# top_schem_rev4.net
KiCad netlist of a schematic drawn in Altium Designer
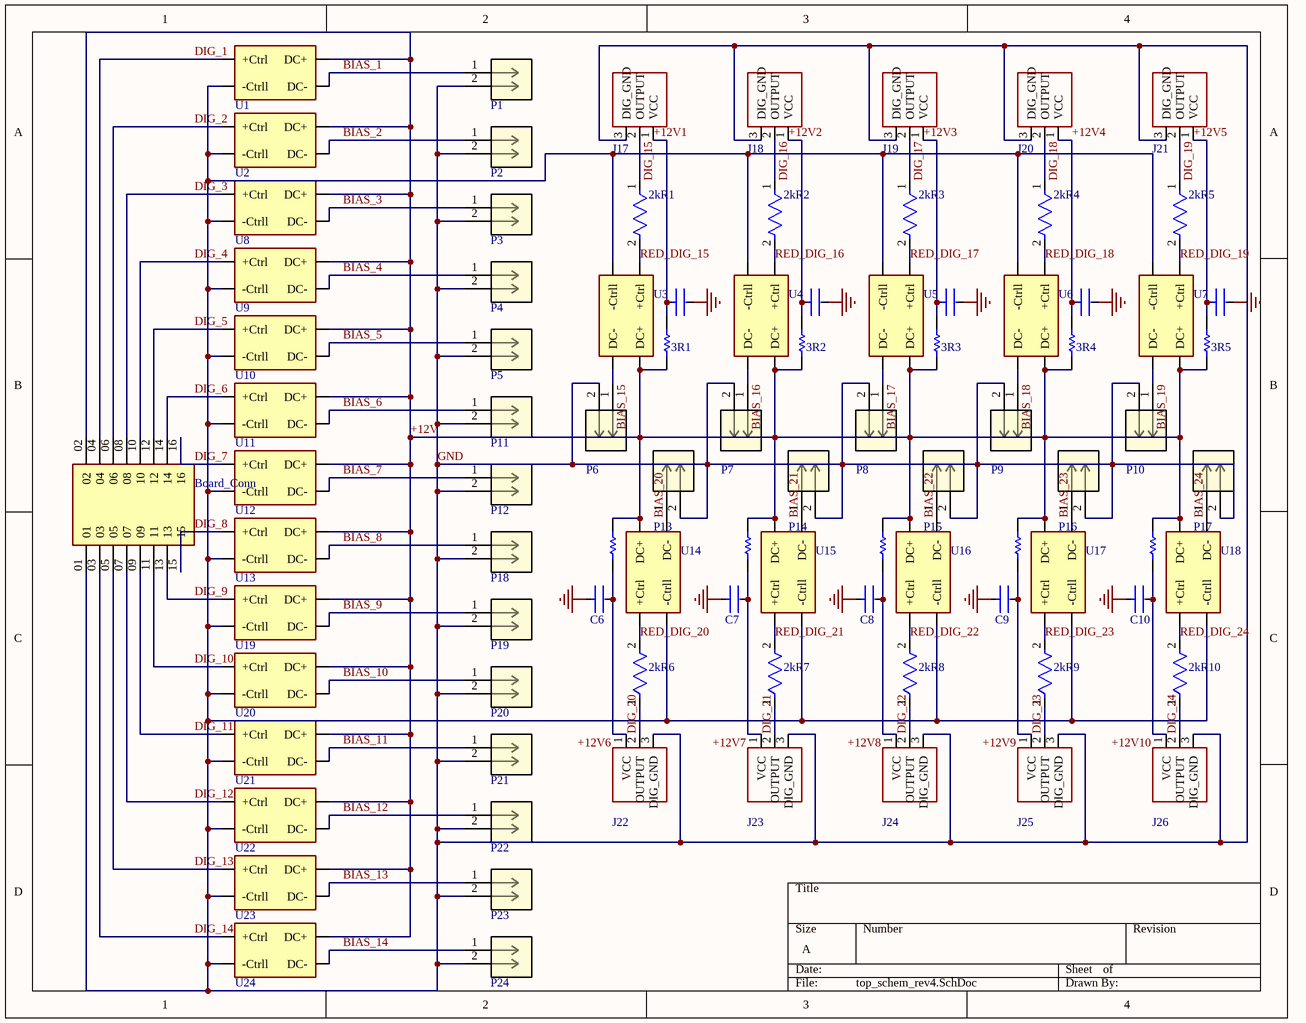
[diagram p0: top_schem_rev4.SchDoc]

(export (version "E")
  (design (tool "Eeschema 10.0.6"))
  (components
    (comp (ref "2kR1")
      (value "CRCW06031K80FKEA")
      (footprint "2kOhm")
      (description "Res Thick Film 0603 1.8K Ohm 1% 1/10W ±100ppm/°C Molded SMD Paper T/R")
      (fields (field (name "MANUFACTURER") "Vishay") (field (name "TOLERANCE") "1%"))
      (libsource (lib "ps_schlib") (part "CRCW06031K80FKEA"))
    )
    (comp (ref "2kR2")
      (value "CRCW06031K80FKEA")
      (footprint "2kOhm")
      (description "Res Thick Film 0603 1.8K Ohm 1% 1/10W ±100ppm/°C Molded SMD Paper T/R")
      (fields (field (name "MANUFACTURER") "Vishay") (field (name "TOLERANCE") "1%"))
      (libsource (lib "ps_schlib") (part "CRCW06031K80FKEA"))
    )
    (comp (ref "2kR3")
      (value "CRCW06031K80FKEA")
      (footprint "2kOhm")
      (description "Res Thick Film 0603 1.8K Ohm 1% 1/10W ±100ppm/°C Molded SMD Paper T/R")
      (fields (field (name "MANUFACTURER") "Vishay") (field (name "TOLERANCE") "1%"))
      (libsource (lib "ps_schlib") (part "CRCW06031K80FKEA"))
    )
    (comp (ref "2kR4")
      (value "CRCW06031K80FKEA")
      (footprint "2kOhm")
      (description "Res Thick Film 0603 1.8K Ohm 1% 1/10W ±100ppm/°C Molded SMD Paper T/R")
      (fields (field (name "MANUFACTURER") "Vishay") (field (name "TOLERANCE") "1%"))
      (libsource (lib "ps_schlib") (part "CRCW06031K80FKEA"))
    )
    (comp (ref "2kR5")
      (value "CRCW06031K80FKEA")
      (footprint "2kOhm")
      (description "Res Thick Film 0603 1.8K Ohm 1% 1/10W ±100ppm/°C Molded SMD Paper T/R")
      (fields (field (name "MANUFACTURER") "Vishay") (field (name "TOLERANCE") "1%"))
      (libsource (lib "ps_schlib") (part "CRCW06031K80FKEA"))
    )
    (comp (ref "2kR6")
      (value "CRCW06031K80FKEA")
      (footprint "2kOhm")
      (description "Res Thick Film 0603 1.8K Ohm 1% 1/10W ±100ppm/°C Molded SMD Paper T/R")
      (fields (field (name "MANUFACTURER") "Vishay") (field (name "TOLERANCE") "1%"))
      (libsource (lib "ps_schlib") (part "CRCW06031K80FKEA"))
    )
    (comp (ref "2kR7")
      (value "CRCW06031K80FKEA")
      (footprint "2kOhm")
      (description "Res Thick Film 0603 1.8K Ohm 1% 1/10W ±100ppm/°C Molded SMD Paper T/R")
      (fields (field (name "MANUFACTURER") "Vishay") (field (name "TOLERANCE") "1%"))
      (libsource (lib "ps_schlib") (part "CRCW06031K80FKEA"))
    )
    (comp (ref "2kR8")
      (value "CRCW06031K80FKEA")
      (footprint "2kOhm")
      (description "Res Thick Film 0603 1.8K Ohm 1% 1/10W ±100ppm/°C Molded SMD Paper T/R")
      (fields (field (name "MANUFACTURER") "Vishay") (field (name "TOLERANCE") "1%"))
      (libsource (lib "ps_schlib") (part "CRCW06031K80FKEA"))
    )
    (comp (ref "2kR9")
      (value "CRCW06031K80FKEA")
      (footprint "2kOhm")
      (description "Res Thick Film 0603 1.8K Ohm 1% 1/10W ±100ppm/°C Molded SMD Paper T/R")
      (fields (field (name "MANUFACTURER") "Vishay") (field (name "TOLERANCE") "1%"))
      (libsource (lib "ps_schlib") (part "CRCW06031K80FKEA"))
    )
    (comp (ref "2kR10")
      (value "CRCW06031K80FKEA")
      (footprint "2kOhm")
      (description "Res Thick Film 0603 1.8K Ohm 1% 1/10W ±100ppm/°C Molded SMD Paper T/R")
      (fields (field (name "MANUFACTURER") "Vishay") (field (name "TOLERANCE") "1%"))
      (libsource (lib "ps_schlib") (part "CRCW06031K80FKEA"))
    )
    (comp (ref "3R1")
      (value "ERJ-2BQJR30X")
      (footprint "03 Ohm")
      (description "RES 0.3 OHM 5% 1/6W 0402")
      (fields (field (name "MANUFACTURER") "Panasonic") (field (name "TOLERANCE") "5%"))
      (libsource (lib "ps_schlib") (part "ERJ-2BQJR30X"))
    )
    (comp (ref "3R2")
      (value "ERJ-2BQJR30X")
      (footprint "03 Ohm")
      (description "RES 0.3 OHM 5% 1/6W 0402")
      (fields (field (name "MANUFACTURER") "Panasonic") (field (name "TOLERANCE") "5%"))
      (libsource (lib "ps_schlib") (part "ERJ-2BQJR30X"))
    )
    (comp (ref "3R3")
      (value "ERJ-2BQJR30X")
      (footprint "03 Ohm")
      (description "RES 0.3 OHM 5% 1/6W 0402")
      (fields (field (name "MANUFACTURER") "Panasonic") (field (name "TOLERANCE") "5%"))
      (libsource (lib "ps_schlib") (part "ERJ-2BQJR30X"))
    )
    (comp (ref "3R4")
      (value "ERJ-2BQJR30X")
      (footprint "03 Ohm")
      (description "RES 0.3 OHM 5% 1/6W 0402")
      (fields (field (name "MANUFACTURER") "Panasonic") (field (name "TOLERANCE") "5%"))
      (libsource (lib "ps_schlib") (part "ERJ-2BQJR30X"))
    )
    (comp (ref "3R5")
      (value "ERJ-2BQJR30X")
      (footprint "03 Ohm")
      (description "RES 0.3 OHM 5% 1/6W 0402")
      (fields (field (name "MANUFACTURER") "Panasonic") (field (name "TOLERANCE") "5%"))
      (libsource (lib "ps_schlib") (part "ERJ-2BQJR30X"))
    )
    (comp (ref "3R6")
      (value "ERJ-2BQJR30X")
      (footprint "03 Ohm")
      (description "RES 0.3 OHM 5% 1/6W 0402")
      (fields (field (name "MANUFACTURER") "Panasonic") (field (name "TOLERANCE") "5%"))
      (libsource (lib "ps_schlib") (part "ERJ-2BQJR30X"))
    )
    (comp (ref "3R7")
      (value "ERJ-2BQJR30X")
      (footprint "03 Ohm")
      (description "RES 0.3 OHM 5% 1/6W 0402")
      (fields (field (name "MANUFACTURER") "Panasonic") (field (name "TOLERANCE") "5%"))
      (libsource (lib "ps_schlib") (part "ERJ-2BQJR30X"))
    )
    (comp (ref "3R8")
      (value "ERJ-2BQJR30X")
      (footprint "03 Ohm")
      (description "RES 0.3 OHM 5% 1/6W 0402")
      (fields (field (name "MANUFACTURER") "Panasonic") (field (name "TOLERANCE") "5%"))
      (libsource (lib "ps_schlib") (part "ERJ-2BQJR30X"))
    )
    (comp (ref "3R9")
      (value "ERJ-2BQJR30X")
      (footprint "03 Ohm")
      (description "RES 0.3 OHM 5% 1/6W 0402")
      (fields (field (name "MANUFACTURER") "Panasonic") (field (name "TOLERANCE") "5%"))
      (libsource (lib "ps_schlib") (part "ERJ-2BQJR30X"))
    )
    (comp (ref "3R10")
      (value "ERJ-2BQJR30X")
      (footprint "03 Ohm")
      (description "RES 0.3 OHM 5% 1/6W 0402")
      (fields (field (name "MANUFACTURER") "Panasonic") (field (name "TOLERANCE") "5%"))
      (libsource (lib "ps_schlib") (part "ERJ-2BQJR30X"))
    )
    (comp (ref "Board_Conn")
      (value "SSM-108-X-DV")
      (footprint "16 pin header")
      (libsource (lib "ps_schlib") (part "SSM-108-X-DV"))
    )
    (comp (ref "C1")
      (value "C0805C104K5RACTU")
      (footprint "100nF")
      (description "Cap Ceramic 0.1uF 50V X7R 10% SMD 2.0 x 1.2 mm 125 C Paper T/R")
      (fields (field (name "MANUFACTURER") "KEMET") (field (name "TOLERANCE") "10%"))
      (libsource (lib "ps_schlib") (part "C0805C104K5RACTU"))
    )
    (comp (ref "C2")
      (value "C0805C104K5RACTU")
      (footprint "100nF")
      (description "Cap Ceramic 0.1uF 50V X7R 10% SMD 2.0 x 1.2 mm 125 C Paper T/R")
      (fields (field (name "MANUFACTURER") "KEMET") (field (name "TOLERANCE") "10%"))
      (libsource (lib "ps_schlib") (part "C0805C104K5RACTU"))
    )
    (comp (ref "C3")
      (value "C0805C104K5RACTU")
      (footprint "100nF")
      (description "Cap Ceramic 0.1uF 50V X7R 10% SMD 2.0 x 1.2 mm 125 C Paper T/R")
      (fields (field (name "MANUFACTURER") "KEMET") (field (name "TOLERANCE") "10%"))
      (libsource (lib "ps_schlib") (part "C0805C104K5RACTU"))
    )
    (comp (ref "C4")
      (value "C0805C104K5RACTU")
      (footprint "100nF")
      (description "Cap Ceramic 0.1uF 50V X7R 10% SMD 2.0 x 1.2 mm 125 C Paper T/R")
      (fields (field (name "MANUFACTURER") "KEMET") (field (name "TOLERANCE") "10%"))
      (libsource (lib "ps_schlib") (part "C0805C104K5RACTU"))
    )
    (comp (ref "C5")
      (value "C0805C104K5RACTU")
      (footprint "100nF")
      (description "Cap Ceramic 0.1uF 50V X7R 10% SMD 2.0 x 1.2 mm 125 C Paper T/R")
      (fields (field (name "MANUFACTURER") "KEMET") (field (name "TOLERANCE") "10%"))
      (libsource (lib "ps_schlib") (part "C0805C104K5RACTU"))
    )
    (comp (ref "C6")
      (value "C0805C104K5RACTU")
      (footprint "100nF")
      (description "Cap Ceramic 0.1uF 50V X7R 10% SMD 2.0 x 1.2 mm 125 C Paper T/R")
      (fields (field (name "MANUFACTURER") "KEMET") (field (name "TOLERANCE") "10%"))
      (libsource (lib "ps_schlib") (part "C0805C104K5RACTU"))
    )
    (comp (ref "C7")
      (value "C0805C104K5RACTU")
      (footprint "100nF")
      (description "Cap Ceramic 0.1uF 50V X7R 10% SMD 2.0 x 1.2 mm 125 C Paper T/R")
      (fields (field (name "MANUFACTURER") "KEMET") (field (name "TOLERANCE") "10%"))
      (libsource (lib "ps_schlib") (part "C0805C104K5RACTU"))
    )
    (comp (ref "C8")
      (value "C0805C104K5RACTU")
      (footprint "100nF")
      (description "Cap Ceramic 0.1uF 50V X7R 10% SMD 2.0 x 1.2 mm 125 C Paper T/R")
      (fields (field (name "MANUFACTURER") "KEMET") (field (name "TOLERANCE") "10%"))
      (libsource (lib "ps_schlib") (part "C0805C104K5RACTU"))
    )
    (comp (ref "C9")
      (value "C0805C104K5RACTU")
      (footprint "100nF")
      (description "Cap Ceramic 0.1uF 50V X7R 10% SMD 2.0 x 1.2 mm 125 C Paper T/R")
      (fields (field (name "MANUFACTURER") "KEMET") (field (name "TOLERANCE") "10%"))
      (libsource (lib "ps_schlib") (part "C0805C104K5RACTU"))
    )
    (comp (ref "C10")
      (value "C0805C104K5RACTU")
      (footprint "100nF")
      (description "Cap Ceramic 0.1uF 50V X7R 10% SMD 2.0 x 1.2 mm 125 C Paper T/R")
      (fields (field (name "MANUFACTURER") "KEMET") (field (name "TOLERANCE") "10%"))
      (libsource (lib "ps_schlib") (part "C0805C104K5RACTU"))
    )
    (comp (ref "J17")
      (value "IF-D95T")
      (footprint "IF-D95")
      (description "DETECTOR PHOTOLOGIC TTL/CMOS")
      (fields (field (name "MANUFACTURER") "Industrial Fiber Optics"))
      (libsource (lib "ps_schlib") (part "IF-D95T"))
    )
    (comp (ref "J18")
      (value "IF-D95T")
      (footprint "IF-D95")
      (description "DETECTOR PHOTOLOGIC TTL/CMOS")
      (fields (field (name "MANUFACTURER") "Industrial Fiber Optics"))
      (libsource (lib "ps_schlib") (part "IF-D95T"))
    )
    (comp (ref "J19")
      (value "IF-D95T")
      (footprint "IF-D95")
      (description "DETECTOR PHOTOLOGIC TTL/CMOS")
      (fields (field (name "MANUFACTURER") "Industrial Fiber Optics"))
      (libsource (lib "ps_schlib") (part "IF-D95T"))
    )
    (comp (ref "J20")
      (value "IF-D95T")
      (footprint "IF-D95")
      (description "DETECTOR PHOTOLOGIC TTL/CMOS")
      (fields (field (name "MANUFACTURER") "Industrial Fiber Optics"))
      (libsource (lib "ps_schlib") (part "IF-D95T"))
    )
    (comp (ref "J21")
      (value "IF-D95T")
      (footprint "IF-D95")
      (description "DETECTOR PHOTOLOGIC TTL/CMOS")
      (fields (field (name "MANUFACTURER") "Industrial Fiber Optics"))
      (libsource (lib "ps_schlib") (part "IF-D95T"))
    )
    (comp (ref "J22")
      (value "IF-D95T")
      (footprint "IF-D95")
      (description "DETECTOR PHOTOLOGIC TTL/CMOS")
      (fields (field (name "MANUFACTURER") "Industrial Fiber Optics"))
      (libsource (lib "ps_schlib") (part "IF-D95T"))
    )
    (comp (ref "J23")
      (value "IF-D95T")
      (footprint "IF-D95")
      (description "DETECTOR PHOTOLOGIC TTL/CMOS")
      (fields (field (name "MANUFACTURER") "Industrial Fiber Optics"))
      (libsource (lib "ps_schlib") (part "IF-D95T"))
    )
    (comp (ref "J24")
      (value "IF-D95T")
      (footprint "IF-D95")
      (description "DETECTOR PHOTOLOGIC TTL/CMOS")
      (fields (field (name "MANUFACTURER") "Industrial Fiber Optics"))
      (libsource (lib "ps_schlib") (part "IF-D95T"))
    )
    (comp (ref "J25")
      (value "IF-D95T")
      (footprint "IF-D95")
      (description "DETECTOR PHOTOLOGIC TTL/CMOS")
      (fields (field (name "MANUFACTURER") "Industrial Fiber Optics"))
      (libsource (lib "ps_schlib") (part "IF-D95T"))
    )
    (comp (ref "J26")
      (value "IF-D95T")
      (footprint "IF-D95")
      (description "DETECTOR PHOTOLOGIC TTL/CMOS")
      (fields (field (name "MANUFACTURER") "Industrial Fiber Optics"))
      (libsource (lib "ps_schlib") (part "IF-D95T"))
    )
    (comp (ref "P1")
      (value "1054311102")
      (footprint "CONN_1054311102_MOL")
      (fields (field (name "MANUFACTURER") "Molex"))
      (libsource (lib "ps_schlib") (part "1054311102"))
    )
    (comp (ref "P2")
      (value "1054311102")
      (footprint "CONN_1054311102_MOL")
      (fields (field (name "MANUFACTURER") "Molex"))
      (libsource (lib "ps_schlib") (part "1054311102"))
    )
    (comp (ref "P3")
      (value "1054311102")
      (footprint "CONN_1054311102_MOL")
      (fields (field (name "MANUFACTURER") "Molex"))
      (libsource (lib "ps_schlib") (part "1054311102"))
    )
    (comp (ref "P4")
      (value "1054311102")
      (footprint "CONN_1054311102_MOL")
      (fields (field (name "MANUFACTURER") "Molex"))
      (libsource (lib "ps_schlib") (part "1054311102"))
    )
    (comp (ref "P5")
      (value "1054311102")
      (footprint "CONN_1054311102_MOL")
      (fields (field (name "MANUFACTURER") "Molex"))
      (libsource (lib "ps_schlib") (part "1054311102"))
    )
    (comp (ref "P6")
      (value "1054311102")
      (footprint "CONN_1054311102_MOL")
      (fields (field (name "MANUFACTURER") "Molex"))
      (libsource (lib "") (part "1054311102_1"))
    )
    (comp (ref "P7")
      (value "1054311102")
      (footprint "CONN_1054311102_MOL")
      (fields (field (name "MANUFACTURER") "Molex"))
      (libsource (lib "") (part "1054311102_1"))
    )
    (comp (ref "P8")
      (value "1054311102")
      (footprint "CONN_1054311102_MOL")
      (fields (field (name "MANUFACTURER") "Molex"))
      (libsource (lib "") (part "1054311102_1"))
    )
    (comp (ref "P9")
      (value "1054311102")
      (footprint "CONN_1054311102_MOL")
      (fields (field (name "MANUFACTURER") "Molex"))
      (libsource (lib "") (part "1054311102_1"))
    )
    (comp (ref "P10")
      (value "1054311102")
      (footprint "CONN_1054311102_MOL")
      (fields (field (name "MANUFACTURER") "Molex"))
      (libsource (lib "") (part "1054311102_1"))
    )
    (comp (ref "P11")
      (value "1054311102")
      (footprint "CONN_1054311102_MOL")
      (fields (field (name "MANUFACTURER") "Molex"))
      (libsource (lib "ps_schlib") (part "1054311102"))
    )
    (comp (ref "P12")
      (value "1054311102")
      (footprint "CONN_1054311102_MOL")
      (fields (field (name "MANUFACTURER") "Molex"))
      (libsource (lib "ps_schlib") (part "1054311102"))
    )
    (comp (ref "P13")
      (value "1054311102")
      (footprint "CONN_1054311102_MOL")
      (fields (field (name "MANUFACTURER") "Molex"))
      (libsource (lib "") (part "1054311102_2"))
    )
    (comp (ref "P14")
      (value "1054311102")
      (footprint "CONN_1054311102_MOL")
      (fields (field (name "MANUFACTURER") "Molex"))
      (libsource (lib "") (part "1054311102_2"))
    )
    (comp (ref "P15")
      (value "1054311102")
      (footprint "CONN_1054311102_MOL")
      (fields (field (name "MANUFACTURER") "Molex"))
      (libsource (lib "") (part "1054311102_2"))
    )
    (comp (ref "P16")
      (value "1054311102")
      (footprint "CONN_1054311102_MOL")
      (fields (field (name "MANUFACTURER") "Molex"))
      (libsource (lib "") (part "1054311102_2"))
    )
    (comp (ref "P17")
      (value "1054311102")
      (footprint "CONN_1054311102_MOL")
      (fields (field (name "MANUFACTURER") "Molex"))
      (libsource (lib "") (part "1054311102_2"))
    )
    (comp (ref "P18")
      (value "1054311102")
      (footprint "CONN_1054311102_MOL")
      (fields (field (name "MANUFACTURER") "Molex"))
      (libsource (lib "ps_schlib") (part "1054311102"))
    )
    (comp (ref "P19")
      (value "1054311102")
      (footprint "CONN_1054311102_MOL")
      (fields (field (name "MANUFACTURER") "Molex"))
      (libsource (lib "ps_schlib") (part "1054311102"))
    )
    (comp (ref "P20")
      (value "1054311102")
      (footprint "CONN_1054311102_MOL")
      (fields (field (name "MANUFACTURER") "Molex"))
      (libsource (lib "ps_schlib") (part "1054311102"))
    )
    (comp (ref "P21")
      (value "1054311102")
      (footprint "CONN_1054311102_MOL")
      (fields (field (name "MANUFACTURER") "Molex"))
      (libsource (lib "ps_schlib") (part "1054311102"))
    )
    (comp (ref "P22")
      (value "1054311102")
      (footprint "CONN_1054311102_MOL")
      (fields (field (name "MANUFACTURER") "Molex"))
      (libsource (lib "ps_schlib") (part "1054311102"))
    )
    (comp (ref "P23")
      (value "1054311102")
      (footprint "CONN_1054311102_MOL")
      (fields (field (name "MANUFACTURER") "Molex"))
      (libsource (lib "ps_schlib") (part "1054311102"))
    )
    (comp (ref "P24")
      (value "1054311102")
      (footprint "CONN_1054311102_MOL")
      (fields (field (name "MANUFACTURER") "Molex"))
      (libsource (lib "ps_schlib") (part "1054311102"))
    )
    (comp (ref "U1")
      (value "Solid state relay")
      (footprint "CPC1002N")
      (libsource (lib "") (part "CPC1002N_1"))
    )
    (comp (ref "U2")
      (value "Solid state relay")
      (footprint "CPC1002N")
      (libsource (lib "") (part "CPC1002N_1"))
    )
    (comp (ref "U3")
      (value "Solid state relay")
      (footprint "CPC1002N")
      (libsource (lib "") (part "CPC1002N_2"))
    )
    (comp (ref "U4")
      (value "Solid state relay")
      (footprint "CPC1002N")
      (libsource (lib "") (part "CPC1002N_2"))
    )
    (comp (ref "U5")
      (value "Solid state relay")
      (footprint "CPC1002N")
      (libsource (lib "") (part "CPC1002N_2"))
    )
    (comp (ref "U6")
      (value "Solid state relay")
      (footprint "CPC1002N")
      (libsource (lib "") (part "CPC1002N_2"))
    )
    (comp (ref "U7")
      (value "Solid state relay")
      (footprint "CPC1002N")
      (libsource (lib "") (part "CPC1002N_2"))
    )
    (comp (ref "U8")
      (value "Solid state relay")
      (footprint "CPC1002N")
      (libsource (lib "") (part "CPC1002N_1"))
    )
    (comp (ref "U9")
      (value "Solid state relay")
      (footprint "CPC1002N")
      (libsource (lib "") (part "CPC1002N_1"))
    )
    (comp (ref "U10")
      (value "Solid state relay")
      (footprint "CPC1002N")
      (libsource (lib "") (part "CPC1002N_1"))
    )
    (comp (ref "U11")
      (value "Solid state relay")
      (footprint "CPC1002N")
      (libsource (lib "") (part "CPC1002N_1"))
    )
    (comp (ref "U12")
      (value "Solid state relay")
      (footprint "CPC1002N")
      (libsource (lib "") (part "CPC1002N_1"))
    )
    (comp (ref "U13")
      (value "Solid state relay")
      (footprint "CPC1002N")
      (libsource (lib "") (part "CPC1002N_1"))
    )
    (comp (ref "U14")
      (value "Solid state relay")
      (footprint "CPC1002N")
      (libsource (lib "ps_schlib") (part "CPC1002N"))
    )
    (comp (ref "U15")
      (value "Solid state relay")
      (footprint "CPC1002N")
      (libsource (lib "ps_schlib") (part "CPC1002N"))
    )
    (comp (ref "U16")
      (value "Solid state relay")
      (footprint "CPC1002N")
      (libsource (lib "ps_schlib") (part "CPC1002N"))
    )
    (comp (ref "U17")
      (value "Solid state relay")
      (footprint "CPC1002N")
      (libsource (lib "ps_schlib") (part "CPC1002N"))
    )
    (comp (ref "U18")
      (value "Solid state relay")
      (footprint "CPC1002N")
      (libsource (lib "ps_schlib") (part "CPC1002N"))
    )
    (comp (ref "U19")
      (value "Solid state relay")
      (footprint "CPC1002N")
      (libsource (lib "") (part "CPC1002N_1"))
    )
    (comp (ref "U20")
      (value "Solid state relay")
      (footprint "CPC1002N")
      (libsource (lib "") (part "CPC1002N_1"))
    )
    (comp (ref "U21")
      (value "Solid state relay")
      (footprint "CPC1002N")
      (libsource (lib "") (part "CPC1002N_1"))
    )
    (comp (ref "U22")
      (value "Solid state relay")
      (footprint "CPC1002N")
      (libsource (lib "") (part "CPC1002N_1"))
    )
    (comp (ref "U23")
      (value "Solid state relay")
      (footprint "CPC1002N")
      (libsource (lib "") (part "CPC1002N_1"))
    )
    (comp (ref "U24")
      (value "Solid state relay")
      (footprint "CPC1002N")
      (libsource (lib "") (part "CPC1002N_1"))
    )
  )
  (nets
    (net (code "1") (name "/+12V") (class "Default")
      (node (ref "3R1") (pin "1") (pinfunction "1_1") (pintype "passive"))
      (node (ref "3R10") (pin "2") (pinfunction "2_2") (pintype "passive"))
      (node (ref "3R2") (pin "1") (pinfunction "1_1") (pintype "passive"))
      (node (ref "3R3") (pin "1") (pinfunction "1_1") (pintype "passive"))
      (node (ref "3R4") (pin "1") (pinfunction "1_1") (pintype "passive"))
      (node (ref "3R5") (pin "1") (pinfunction "1_1") (pintype "passive"))
      (node (ref "3R6") (pin "2") (pinfunction "2_2") (pintype "passive"))
      (node (ref "3R7") (pin "2") (pinfunction "2_2") (pintype "passive"))
      (node (ref "3R8") (pin "2") (pinfunction "2_2") (pintype "passive"))
      (node (ref "3R9") (pin "2") (pinfunction "2_2") (pintype "passive"))
      (node (ref "Board_Conn") (pin "02") (pinfunction "02_02") (pintype "passive"))
      (node (ref "U1") (pin "4") (pinfunction "DC+_4") (pintype "passive"))
      (node (ref "U10") (pin "4") (pinfunction "DC+_4") (pintype "passive"))
      (node (ref "U11") (pin "4") (pinfunction "DC+_4") (pintype "passive"))
      (node (ref "U12") (pin "4") (pinfunction "DC+_4") (pintype "passive"))
      (node (ref "U13") (pin "4") (pinfunction "DC+_4") (pintype "passive"))
      (node (ref "U14") (pin "4") (pinfunction "DC+_4") (pintype "passive"))
      (node (ref "U15") (pin "4") (pinfunction "DC+_4") (pintype "passive"))
      (node (ref "U16") (pin "4") (pinfunction "DC+_4") (pintype "passive"))
      (node (ref "U17") (pin "4") (pinfunction "DC+_4") (pintype "passive"))
      (node (ref "U18") (pin "4") (pinfunction "DC+_4") (pintype "passive"))
      (node (ref "U19") (pin "4") (pinfunction "DC+_4") (pintype "passive"))
      (node (ref "U2") (pin "4") (pinfunction "DC+_4") (pintype "passive"))
      (node (ref "U20") (pin "4") (pinfunction "DC+_4") (pintype "passive"))
      (node (ref "U21") (pin "4") (pinfunction "DC+_4") (pintype "passive"))
      (node (ref "U22") (pin "4") (pinfunction "DC+_4") (pintype "passive"))
      (node (ref "U23") (pin "4") (pinfunction "DC+_4") (pintype "passive"))
      (node (ref "U24") (pin "4") (pinfunction "DC+_4") (pintype "passive"))
      (node (ref "U3") (pin "4") (pinfunction "DC+_4") (pintype "passive"))
      (node (ref "U4") (pin "4") (pinfunction "DC+_4") (pintype "passive"))
      (node (ref "U5") (pin "4") (pinfunction "DC+_4") (pintype "passive"))
      (node (ref "U6") (pin "4") (pinfunction "DC+_4") (pintype "passive"))
      (node (ref "U7") (pin "4") (pinfunction "DC+_4") (pintype "passive"))
      (node (ref "U8") (pin "4") (pinfunction "DC+_4") (pintype "passive"))
      (node (ref "U9") (pin "4") (pinfunction "DC+_4") (pintype "passive"))
    )
    (net (code "2") (name "/+12V1") (class "Default")
      (node (ref "3R1") (pin "2") (pinfunction "2_2") (pintype "passive"))
      (node (ref "C1") (pin "1") (pinfunction "1_1") (pintype "passive"))
      (node (ref "J17") (pin "1") (pinfunction "VCC_1") (pintype "passive"))
    )
    (net (code "3") (name "/+12V2") (class "Default")
      (node (ref "3R2") (pin "2") (pinfunction "2_2") (pintype "passive"))
      (node (ref "C2") (pin "1") (pinfunction "1_1") (pintype "passive"))
      (node (ref "J18") (pin "1") (pinfunction "VCC_1") (pintype "passive"))
    )
    (net (code "4") (name "/+12V3") (class "Default")
      (node (ref "3R3") (pin "2") (pinfunction "2_2") (pintype "passive"))
      (node (ref "C3") (pin "1") (pinfunction "1_1") (pintype "passive"))
      (node (ref "J19") (pin "1") (pinfunction "VCC_1") (pintype "passive"))
    )
    (net (code "5") (name "/+12V4") (class "Default")
      (node (ref "3R4") (pin "2") (pinfunction "2_2") (pintype "passive"))
      (node (ref "C4") (pin "1") (pinfunction "1_1") (pintype "passive"))
      (node (ref "J20") (pin "1") (pinfunction "VCC_1") (pintype "passive"))
    )
    (net (code "6") (name "/+12V5") (class "Default")
      (node (ref "3R5") (pin "2") (pinfunction "2_2") (pintype "passive"))
      (node (ref "C5") (pin "1") (pinfunction "1_1") (pintype "passive"))
      (node (ref "J21") (pin "1") (pinfunction "VCC_1") (pintype "passive"))
    )
    (net (code "7") (name "/+12V6") (class "Default")
      (node (ref "3R6") (pin "1") (pinfunction "1_1") (pintype "passive"))
      (node (ref "C6") (pin "2") (pinfunction "2_2") (pintype "passive"))
      (node (ref "J22") (pin "1") (pinfunction "VCC_1") (pintype "passive"))
    )
    (net (code "8") (name "/+12V7") (class "Default")
      (node (ref "3R7") (pin "1") (pinfunction "1_1") (pintype "passive"))
      (node (ref "C7") (pin "2") (pinfunction "2_2") (pintype "passive"))
      (node (ref "J23") (pin "1") (pinfunction "VCC_1") (pintype "passive"))
    )
    (net (code "9") (name "/+12V8") (class "Default")
      (node (ref "3R8") (pin "1") (pinfunction "1_1") (pintype "passive"))
      (node (ref "C8") (pin "2") (pinfunction "2_2") (pintype "passive"))
      (node (ref "J24") (pin "1") (pinfunction "VCC_1") (pintype "passive"))
    )
    (net (code "10") (name "/+12V9") (class "Default")
      (node (ref "3R9") (pin "1") (pinfunction "1_1") (pintype "passive"))
      (node (ref "C9") (pin "2") (pinfunction "2_2") (pintype "passive"))
      (node (ref "J25") (pin "1") (pinfunction "VCC_1") (pintype "passive"))
    )
    (net (code "11") (name "/+12V10") (class "Default")
      (node (ref "3R10") (pin "1") (pinfunction "1_1") (pintype "passive"))
      (node (ref "C10") (pin "2") (pinfunction "2_2") (pintype "passive"))
      (node (ref "J26") (pin "1") (pinfunction "VCC_1") (pintype "passive"))
    )
    (net (code "12") (name "/BIAS_1") (class "Default")
      (node (ref "P1") (pin "1") (pinfunction "1_1") (pintype "passive"))
      (node (ref "U1") (pin "3") (pinfunction "DC-_3") (pintype "passive"))
    )
    (net (code "13") (name "/BIAS_2") (class "Default")
      (node (ref "P2") (pin "1") (pinfunction "1_1") (pintype "passive"))
      (node (ref "U2") (pin "3") (pinfunction "DC-_3") (pintype "passive"))
    )
    (net (code "14") (name "/BIAS_3") (class "Default")
      (node (ref "P3") (pin "1") (pinfunction "1_1") (pintype "passive"))
      (node (ref "U8") (pin "3") (pinfunction "DC-_3") (pintype "passive"))
    )
    (net (code "15") (name "/BIAS_4") (class "Default")
      (node (ref "P4") (pin "1") (pinfunction "1_1") (pintype "passive"))
      (node (ref "U9") (pin "3") (pinfunction "DC-_3") (pintype "passive"))
    )
    (net (code "16") (name "/BIAS_5") (class "Default")
      (node (ref "P5") (pin "1") (pinfunction "1_1") (pintype "passive"))
      (node (ref "U10") (pin "3") (pinfunction "DC-_3") (pintype "passive"))
    )
    (net (code "17") (name "/BIAS_6") (class "Default")
      (node (ref "P11") (pin "1") (pinfunction "1_1") (pintype "passive"))
      (node (ref "U11") (pin "3") (pinfunction "DC-_3") (pintype "passive"))
    )
    (net (code "18") (name "/BIAS_7") (class "Default")
      (node (ref "P12") (pin "1") (pinfunction "1_1") (pintype "passive"))
      (node (ref "U12") (pin "3") (pinfunction "DC-_3") (pintype "passive"))
    )
    (net (code "19") (name "/BIAS_8") (class "Default")
      (node (ref "P18") (pin "1") (pinfunction "1_1") (pintype "passive"))
      (node (ref "U13") (pin "3") (pinfunction "DC-_3") (pintype "passive"))
    )
    (net (code "20") (name "/BIAS_9") (class "Default")
      (node (ref "P19") (pin "1") (pinfunction "1_1") (pintype "passive"))
      (node (ref "U19") (pin "3") (pinfunction "DC-_3") (pintype "passive"))
    )
    (net (code "21") (name "/BIAS_10") (class "Default")
      (node (ref "P20") (pin "1") (pinfunction "1_1") (pintype "passive"))
      (node (ref "U20") (pin "3") (pinfunction "DC-_3") (pintype "passive"))
    )
    (net (code "22") (name "/BIAS_11") (class "Default")
      (node (ref "P21") (pin "1") (pinfunction "1_1") (pintype "passive"))
      (node (ref "U21") (pin "3") (pinfunction "DC-_3") (pintype "passive"))
    )
    (net (code "23") (name "/BIAS_12") (class "Default")
      (node (ref "P22") (pin "1") (pinfunction "1_1") (pintype "passive"))
      (node (ref "U22") (pin "3") (pinfunction "DC-_3") (pintype "passive"))
    )
    (net (code "24") (name "/BIAS_13") (class "Default")
      (node (ref "P23") (pin "1") (pinfunction "1_1") (pintype "passive"))
      (node (ref "U23") (pin "3") (pinfunction "DC-_3") (pintype "passive"))
    )
    (net (code "25") (name "/BIAS_14") (class "Default")
      (node (ref "P24") (pin "1") (pinfunction "1_1") (pintype "passive"))
      (node (ref "U24") (pin "3") (pinfunction "DC-_3") (pintype "passive"))
    )
    (net (code "26") (name "/BIAS_15") (class "Default")
      (node (ref "P6") (pin "1") (pinfunction "1_1") (pintype "passive"))
      (node (ref "U3") (pin "3") (pinfunction "DC-_3") (pintype "passive"))
    )
    (net (code "27") (name "/BIAS_16") (class "Default")
      (node (ref "P7") (pin "1") (pinfunction "1_1") (pintype "passive"))
      (node (ref "U4") (pin "3") (pinfunction "DC-_3") (pintype "passive"))
    )
    (net (code "28") (name "/BIAS_17") (class "Default")
      (node (ref "P8") (pin "1") (pinfunction "1_1") (pintype "passive"))
      (node (ref "U5") (pin "3") (pinfunction "DC-_3") (pintype "passive"))
    )
    (net (code "29") (name "/BIAS_18") (class "Default")
      (node (ref "P9") (pin "1") (pinfunction "1_1") (pintype "passive"))
      (node (ref "U6") (pin "3") (pinfunction "DC-_3") (pintype "passive"))
    )
    (net (code "30") (name "/BIAS_19") (class "Default")
      (node (ref "P10") (pin "1") (pinfunction "1_1") (pintype "passive"))
      (node (ref "U7") (pin "3") (pinfunction "DC-_3") (pintype "passive"))
    )
    (net (code "31") (name "/BIAS_20") (class "Default")
      (node (ref "P13") (pin "1") (pinfunction "1_1") (pintype "passive"))
      (node (ref "U14") (pin "3") (pinfunction "DC-_3") (pintype "passive"))
    )
    (net (code "32") (name "/BIAS_21") (class "Default")
      (node (ref "P14") (pin "1") (pinfunction "1_1") (pintype "passive"))
      (node (ref "U15") (pin "3") (pinfunction "DC-_3") (pintype "passive"))
    )
    (net (code "33") (name "/BIAS_22") (class "Default")
      (node (ref "P15") (pin "1") (pinfunction "1_1") (pintype "passive"))
      (node (ref "U16") (pin "3") (pinfunction "DC-_3") (pintype "passive"))
    )
    (net (code "34") (name "/BIAS_23") (class "Default")
      (node (ref "P16") (pin "1") (pinfunction "1_1") (pintype "passive"))
      (node (ref "U17") (pin "3") (pinfunction "DC-_3") (pintype "passive"))
    )
    (net (code "35") (name "/BIAS_24") (class "Default")
      (node (ref "P17") (pin "1") (pinfunction "1_1") (pintype "passive"))
      (node (ref "U18") (pin "3") (pinfunction "DC-_3") (pintype "passive"))
    )
    (net (code "36") (name "/DIG_1") (class "Default")
      (node (ref "Board_Conn") (pin "04") (pinfunction "04_04") (pintype "passive"))
      (node (ref "U1") (pin "1") (pinfunction "+Ctrl_1") (pintype "passive"))
    )
    (net (code "37") (name "/DIG_2") (class "Default")
      (node (ref "Board_Conn") (pin "06") (pinfunction "06_06") (pintype "passive"))
      (node (ref "U2") (pin "1") (pinfunction "+Ctrl_1") (pintype "passive"))
    )
    (net (code "38") (name "/DIG_3") (class "Default")
      (node (ref "Board_Conn") (pin "08") (pinfunction "08_08") (pintype "passive"))
      (node (ref "U8") (pin "1") (pinfunction "+Ctrl_1") (pintype "passive"))
    )
    (net (code "39") (name "/DIG_4") (class "Default")
      (node (ref "Board_Conn") (pin "10") (pinfunction "10_10") (pintype "passive"))
      (node (ref "U9") (pin "1") (pinfunction "+Ctrl_1") (pintype "passive"))
    )
    (net (code "40") (name "/DIG_5") (class "Default")
      (node (ref "Board_Conn") (pin "12") (pinfunction "12_12") (pintype "passive"))
      (node (ref "U10") (pin "1") (pinfunction "+Ctrl_1") (pintype "passive"))
    )
    (net (code "41") (name "/DIG_6") (class "Default")
      (node (ref "Board_Conn") (pin "14") (pinfunction "14_14") (pintype "passive"))
      (node (ref "U11") (pin "1") (pinfunction "+Ctrl_1") (pintype "passive"))
    )
    (net (code "42") (name "/DIG_7") (class "Default")
      (node (ref "Board_Conn") (pin "16") (pinfunction "16_16") (pintype "passive"))
      (node (ref "U12") (pin "1") (pinfunction "+Ctrl_1") (pintype "passive"))
    )
    (net (code "43") (name "/DIG_8") (class "Default")
      (node (ref "Board_Conn") (pin "15") (pinfunction "15_15") (pintype "passive"))
      (node (ref "U13") (pin "1") (pinfunction "+Ctrl_1") (pintype "passive"))
    )
    (net (code "44") (name "/DIG_9") (class "Default")
      (node (ref "Board_Conn") (pin "13") (pinfunction "13_13") (pintype "passive"))
      (node (ref "U19") (pin "1") (pinfunction "+Ctrl_1") (pintype "passive"))
    )
    (net (code "45") (name "/DIG_10") (class "Default")
      (node (ref "Board_Conn") (pin "11") (pinfunction "11_11") (pintype "passive"))
      (node (ref "U20") (pin "1") (pinfunction "+Ctrl_1") (pintype "passive"))
    )
    (net (code "46") (name "/DIG_11") (class "Default")
      (node (ref "Board_Conn") (pin "09") (pinfunction "09_09") (pintype "passive"))
      (node (ref "U21") (pin "1") (pinfunction "+Ctrl_1") (pintype "passive"))
    )
    (net (code "47") (name "/DIG_12") (class "Default")
      (node (ref "Board_Conn") (pin "07") (pinfunction "07_07") (pintype "passive"))
      (node (ref "U22") (pin "1") (pinfunction "+Ctrl_1") (pintype "passive"))
    )
    (net (code "48") (name "/DIG_13") (class "Default")
      (node (ref "Board_Conn") (pin "05") (pinfunction "05_05") (pintype "passive"))
      (node (ref "U23") (pin "1") (pinfunction "+Ctrl_1") (pintype "passive"))
    )
    (net (code "49") (name "/DIG_14") (class "Default")
      (node (ref "Board_Conn") (pin "03") (pinfunction "03_03") (pintype "passive"))
      (node (ref "U24") (pin "1") (pinfunction "+Ctrl_1") (pintype "passive"))
    )
    (net (code "50") (name "/DIG_15") (class "Default")
      (node (ref "2kR1") (pin "1") (pinfunction "1_1") (pintype "passive"))
      (node (ref "J17") (pin "2") (pinfunction "OUTPUT_2") (pintype "passive"))
    )
    (net (code "51") (name "/DIG_16") (class "Default")
      (node (ref "2kR2") (pin "1") (pinfunction "1_1") (pintype "passive"))
      (node (ref "J18") (pin "2") (pinfunction "OUTPUT_2") (pintype "passive"))
    )
    (net (code "52") (name "/DIG_17") (class "Default")
      (node (ref "2kR3") (pin "1") (pinfunction "1_1") (pintype "passive"))
      (node (ref "J19") (pin "2") (pinfunction "OUTPUT_2") (pintype "passive"))
    )
    (net (code "53") (name "/DIG_18") (class "Default")
      (node (ref "2kR4") (pin "1") (pinfunction "1_1") (pintype "passive"))
      (node (ref "J20") (pin "2") (pinfunction "OUTPUT_2") (pintype "passive"))
    )
    (net (code "54") (name "/DIG_19") (class "Default")
      (node (ref "2kR5") (pin "1") (pinfunction "1_1") (pintype "passive"))
      (node (ref "J21") (pin "2") (pinfunction "OUTPUT_2") (pintype "passive"))
    )
    (net (code "55") (name "/DIG_20") (class "Default")
      (node (ref "2kR6") (pin "1") (pinfunction "1_1") (pintype "passive"))
      (node (ref "J22") (pin "2") (pinfunction "OUTPUT_2") (pintype "passive"))
    )
    (net (code "56") (name "/DIG_21") (class "Default")
      (node (ref "2kR7") (pin "1") (pinfunction "1_1") (pintype "passive"))
      (node (ref "J23") (pin "2") (pinfunction "OUTPUT_2") (pintype "passive"))
    )
    (net (code "57") (name "/DIG_22") (class "Default")
      (node (ref "2kR8") (pin "1") (pinfunction "1_1") (pintype "passive"))
      (node (ref "J24") (pin "2") (pinfunction "OUTPUT_2") (pintype "passive"))
    )
    (net (code "58") (name "/DIG_23") (class "Default")
      (node (ref "2kR9") (pin "1") (pinfunction "1_1") (pintype "passive"))
      (node (ref "J25") (pin "2") (pinfunction "OUTPUT_2") (pintype "passive"))
    )
    (net (code "59") (name "/DIG_24") (class "Default")
      (node (ref "2kR10") (pin "1") (pinfunction "1_1") (pintype "passive"))
      (node (ref "J26") (pin "2") (pinfunction "OUTPUT_2") (pintype "passive"))
    )
    (net (code "60") (name "/RED_DIG_15") (class "Default")
      (node (ref "2kR1") (pin "2") (pinfunction "2_2") (pintype "passive"))
      (node (ref "U3") (pin "1") (pinfunction "+Ctrl_1") (pintype "passive"))
    )
    (net (code "61") (name "/RED_DIG_16") (class "Default")
      (node (ref "2kR2") (pin "2") (pinfunction "2_2") (pintype "passive"))
      (node (ref "U4") (pin "1") (pinfunction "+Ctrl_1") (pintype "passive"))
    )
    (net (code "62") (name "/RED_DIG_17") (class "Default")
      (node (ref "2kR3") (pin "2") (pinfunction "2_2") (pintype "passive"))
      (node (ref "U5") (pin "1") (pinfunction "+Ctrl_1") (pintype "passive"))
    )
    (net (code "63") (name "/RED_DIG_18") (class "Default")
      (node (ref "2kR4") (pin "2") (pinfunction "2_2") (pintype "passive"))
      (node (ref "U6") (pin "1") (pinfunction "+Ctrl_1") (pintype "passive"))
    )
    (net (code "64") (name "/RED_DIG_19") (class "Default")
      (node (ref "2kR5") (pin "2") (pinfunction "2_2") (pintype "passive"))
      (node (ref "U7") (pin "1") (pinfunction "+Ctrl_1") (pintype "passive"))
    )
    (net (code "65") (name "/RED_DIG_20") (class "Default")
      (node (ref "2kR6") (pin "2") (pinfunction "2_2") (pintype "passive"))
      (node (ref "U14") (pin "1") (pinfunction "+Ctrl_1") (pintype "passive"))
    )
    (net (code "66") (name "/RED_DIG_21") (class "Default")
      (node (ref "2kR7") (pin "2") (pinfunction "2_2") (pintype "passive"))
      (node (ref "U15") (pin "1") (pinfunction "+Ctrl_1") (pintype "passive"))
    )
    (net (code "67") (name "/RED_DIG_22") (class "Default")
      (node (ref "2kR8") (pin "2") (pinfunction "2_2") (pintype "passive"))
      (node (ref "U16") (pin "1") (pinfunction "+Ctrl_1") (pintype "passive"))
    )
    (net (code "68") (name "/RED_DIG_23") (class "Default")
      (node (ref "2kR9") (pin "2") (pinfunction "2_2") (pintype "passive"))
      (node (ref "U17") (pin "1") (pinfunction "+Ctrl_1") (pintype "passive"))
    )
    (net (code "69") (name "/RED_DIG_24") (class "Default")
      (node (ref "2kR10") (pin "2") (pinfunction "2_2") (pintype "passive"))
      (node (ref "U18") (pin "1") (pinfunction "+Ctrl_1") (pintype "passive"))
    )
    (net (code "70") (name "GND") (class "Default")
      (node (ref "Board_Conn") (pin "01") (pinfunction "01_01") (pintype "passive"))
      (node (ref "C1") (pin "2") (pinfunction "2_2") (pintype "passive"))
      (node (ref "C10") (pin "1") (pinfunction "1_1") (pintype "passive"))
      (node (ref "C2") (pin "2") (pinfunction "2_2") (pintype "passive"))
      (node (ref "C3") (pin "2") (pinfunction "2_2") (pintype "passive"))
      (node (ref "C4") (pin "2") (pinfunction "2_2") (pintype "passive"))
      (node (ref "C5") (pin "2") (pinfunction "2_2") (pintype "passive"))
      (node (ref "C6") (pin "1") (pinfunction "1_1") (pintype "passive"))
      (node (ref "C7") (pin "1") (pinfunction "1_1") (pintype "passive"))
      (node (ref "C8") (pin "1") (pinfunction "1_1") (pintype "passive"))
      (node (ref "C9") (pin "1") (pinfunction "1_1") (pintype "passive"))
      (node (ref "J17") (pin "3") (pinfunction "DIG_GND_3") (pintype "passive"))
      (node (ref "J18") (pin "3") (pinfunction "DIG_GND_3") (pintype "passive"))
      (node (ref "J19") (pin "3") (pinfunction "DIG_GND_3") (pintype "passive"))
      (node (ref "J20") (pin "3") (pinfunction "DIG_GND_3") (pintype "passive"))
      (node (ref "J21") (pin "3") (pinfunction "DIG_GND_3") (pintype "passive"))
      (node (ref "J22") (pin "3") (pinfunction "DIG_GND_3") (pintype "passive"))
      (node (ref "J23") (pin "3") (pinfunction "DIG_GND_3") (pintype "passive"))
      (node (ref "J24") (pin "3") (pinfunction "DIG_GND_3") (pintype "passive"))
      (node (ref "J25") (pin "3") (pinfunction "DIG_GND_3") (pintype "passive"))
      (node (ref "J26") (pin "3") (pinfunction "DIG_GND_3") (pintype "passive"))
      (node (ref "P1") (pin "2") (pinfunction "2_2") (pintype "passive"))
      (node (ref "P10") (pin "2") (pinfunction "2_2") (pintype "passive"))
      (node (ref "P11") (pin "2") (pinfunction "2_2") (pintype "passive"))
      (node (ref "P12") (pin "2") (pinfunction "2_2") (pintype "passive"))
      (node (ref "P13") (pin "2") (pinfunction "2_2") (pintype "passive"))
      (node (ref "P14") (pin "2") (pinfunction "2_2") (pintype "passive"))
      (node (ref "P15") (pin "2") (pinfunction "2_2") (pintype "passive"))
      (node (ref "P16") (pin "2") (pinfunction "2_2") (pintype "passive"))
      (node (ref "P17") (pin "2") (pinfunction "2_2") (pintype "passive"))
      (node (ref "P18") (pin "2") (pinfunction "2_2") (pintype "passive"))
      (node (ref "P19") (pin "2") (pinfunction "2_2") (pintype "passive"))
      (node (ref "P2") (pin "2") (pinfunction "2_2") (pintype "passive"))
      (node (ref "P20") (pin "2") (pinfunction "2_2") (pintype "passive"))
      (node (ref "P21") (pin "2") (pinfunction "2_2") (pintype "passive"))
      (node (ref "P22") (pin "2") (pinfunction "2_2") (pintype "passive"))
      (node (ref "P23") (pin "2") (pinfunction "2_2") (pintype "passive"))
      (node (ref "P24") (pin "2") (pinfunction "2_2") (pintype "passive"))
      (node (ref "P3") (pin "2") (pinfunction "2_2") (pintype "passive"))
      (node (ref "P4") (pin "2") (pinfunction "2_2") (pintype "passive"))
      (node (ref "P5") (pin "2") (pinfunction "2_2") (pintype "passive"))
      (node (ref "P6") (pin "2") (pinfunction "2_2") (pintype "passive"))
      (node (ref "P7") (pin "2") (pinfunction "2_2") (pintype "passive"))
      (node (ref "P8") (pin "2") (pinfunction "2_2") (pintype "passive"))
      (node (ref "P9") (pin "2") (pinfunction "2_2") (pintype "passive"))
      (node (ref "U1") (pin "2") (pinfunction "-Ctrll_2") (pintype "passive"))
      (node (ref "U10") (pin "2") (pinfunction "-Ctrll_2") (pintype "passive"))
      (node (ref "U11") (pin "2") (pinfunction "-Ctrll_2") (pintype "passive"))
      (node (ref "U12") (pin "2") (pinfunction "-Ctrll_2") (pintype "passive"))
      (node (ref "U13") (pin "2") (pinfunction "-Ctrll_2") (pintype "passive"))
      (node (ref "U14") (pin "2") (pinfunction "-Ctrll_2") (pintype "passive"))
      (node (ref "U15") (pin "2") (pinfunction "-Ctrll_2") (pintype "passive"))
      (node (ref "U16") (pin "2") (pinfunction "-Ctrll_2") (pintype "passive"))
      (node (ref "U17") (pin "2") (pinfunction "-Ctrll_2") (pintype "passive"))
      (node (ref "U18") (pin "2") (pinfunction "-Ctrll_2") (pintype "passive"))
      (node (ref "U19") (pin "2") (pinfunction "-Ctrll_2") (pintype "passive"))
      (node (ref "U2") (pin "2") (pinfunction "-Ctrll_2") (pintype "passive"))
      (node (ref "U20") (pin "2") (pinfunction "-Ctrll_2") (pintype "passive"))
      (node (ref "U21") (pin "2") (pinfunction "-Ctrll_2") (pintype "passive"))
      (node (ref "U22") (pin "2") (pinfunction "-Ctrll_2") (pintype "passive"))
      (node (ref "U23") (pin "2") (pinfunction "-Ctrll_2") (pintype "passive"))
      (node (ref "U24") (pin "2") (pinfunction "-Ctrll_2") (pintype "passive"))
      (node (ref "U3") (pin "2") (pinfunction "-Ctrll_2") (pintype "passive"))
      (node (ref "U4") (pin "2") (pinfunction "-Ctrll_2") (pintype "passive"))
      (node (ref "U5") (pin "2") (pinfunction "-Ctrll_2") (pintype "passive"))
      (node (ref "U6") (pin "2") (pinfunction "-Ctrll_2") (pintype "passive"))
      (node (ref "U7") (pin "2") (pinfunction "-Ctrll_2") (pintype "passive"))
      (node (ref "U8") (pin "2") (pinfunction "-Ctrll_2") (pintype "passive"))
      (node (ref "U9") (pin "2") (pinfunction "-Ctrll_2") (pintype "passive"))
    )
  )
)
